# Teclado_numerico.net
KiCad netlist of a schematic drawn in Altium Designer
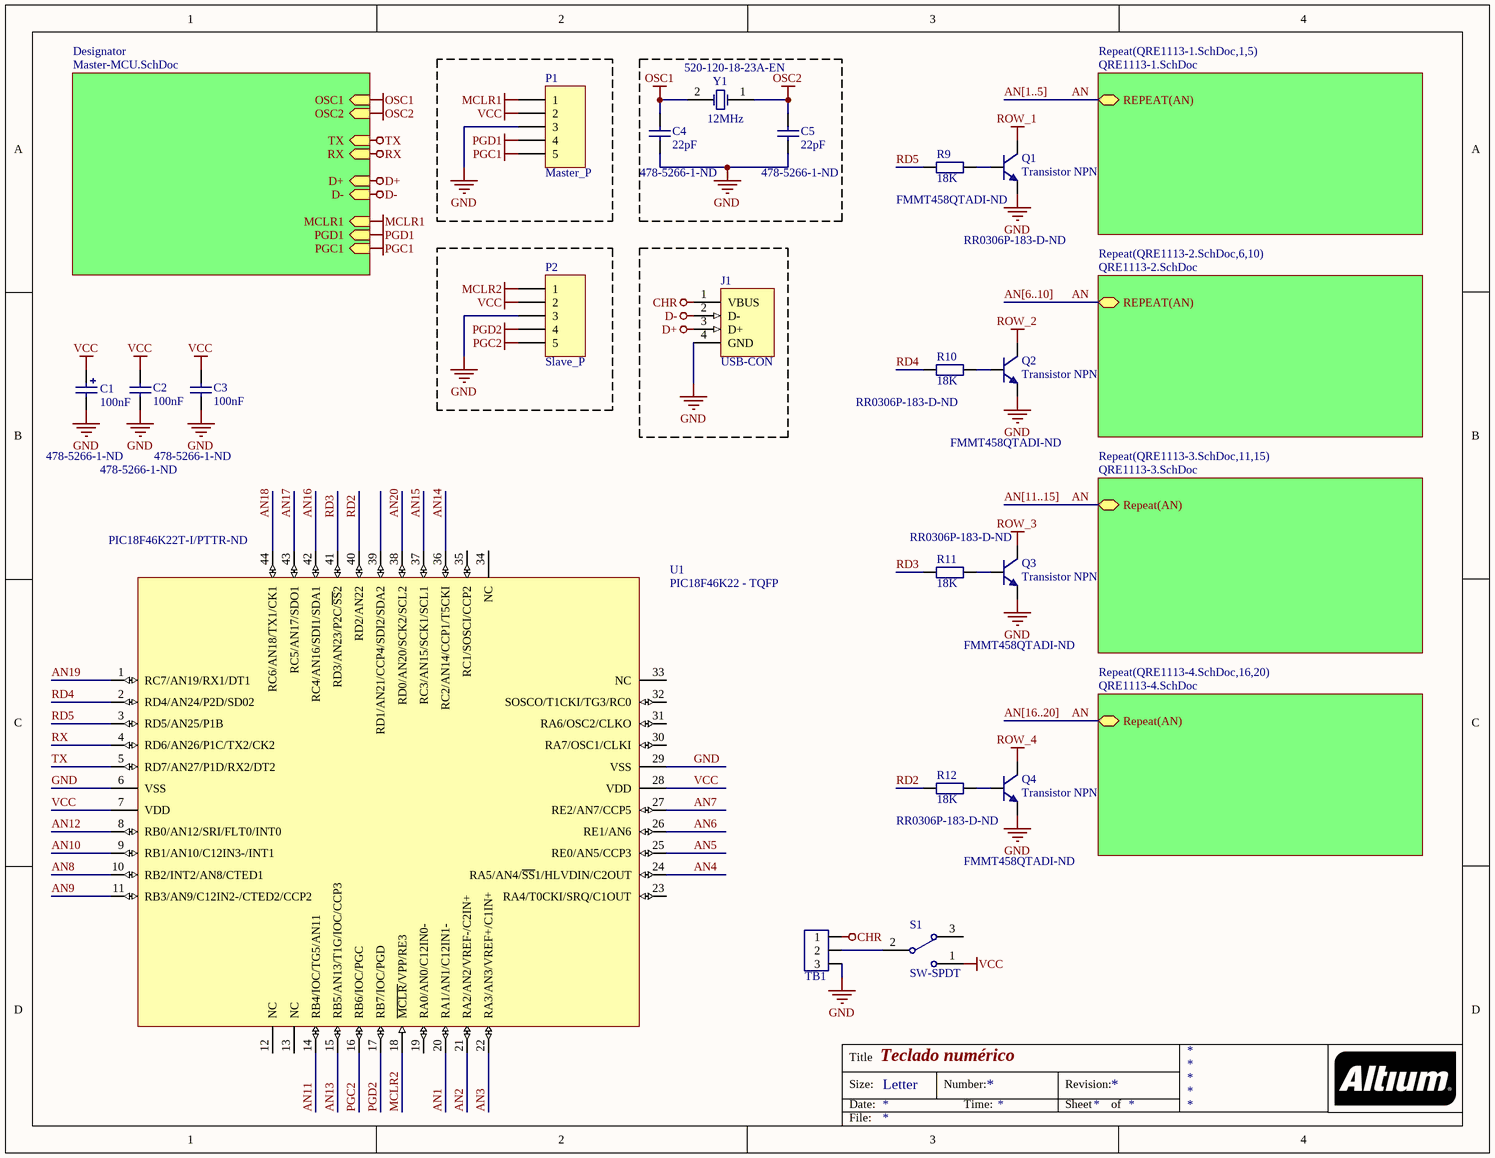
[diagram p0: Teclado numerico.SchDoc]

(export (version "E")
  (design (tool "Eeschema 10.0.6"))
  (components
    (comp (ref "C1")
      (value "100nF")
      (footprint "C-0603")
      (description "Electrolytic Capacitor")
      (fields (field (name "SUPPLIER PART NUMBER 1") "478-5266-1-ND"))
      (libsource (lib "Max Library") (part "Electrolytic Capacitor"))
    )
    (comp (ref "C2")
      (value "100nF")
      (footprint "C-0603")
      (description "Capacitor")
      (fields (field (name "SUPPLIER PART NUMBER 1") "478-5266-1-ND"))
      (libsource (lib "Max Library") (part "Capacitor 1"))
    )
    (comp (ref "C3")
      (value "100nF")
      (footprint "C-0603")
      (description "Capacitor")
      (fields (field (name "SUPPLIER PART NUMBER 1") "478-5266-1-ND"))
      (libsource (lib "Max Library") (part "Capacitor 1"))
    )
    (comp (ref "C4")
      (value "22pF")
      (footprint "C-0603")
      (description "Capacitor")
      (fields (field (name "SUPPLIER PART NUMBER 1") "478-5266-1-ND"))
      (libsource (lib "Max Library") (part "Capacitor 1"))
    )
    (comp (ref "C5")
      (value "22pF")
      (footprint "C-0603")
      (description "Capacitor")
      (fields (field (name "SUPPLIER PART NUMBER 1") "478-5266-1-ND"))
      (libsource (lib "Max Library") (part "Capacitor 1"))
    )
    (comp (ref "J1")
      (value "USB-CON")
      (footprint "JV Footprints:USB-A")
      (description "USB 1.1, Right Angle, SMT, A Type, Receptacle, 4 Position, White")
      (fields (field (name "PUBLISHER") "Altium Limited"))
      (libsource (lib "Max Library") (part "USB-CON"))
    )
    (comp (ref "P1")
      (value "Master_P")
      (footprint "HDR1X5")
      (description "Header, 5-Pin")
      (fields (field (name "PUBLISHER") "Altium Limited"))
      (libsource (lib "Miscellaneous Connectors") (part "Header 5"))
    )
    (comp (ref "P2")
      (value "Slave_P")
      (footprint "HDR1X5")
      (description "Header, 5-Pin")
      (fields (field (name "PUBLISHER") "Altium Limited"))
      (libsource (lib "Miscellaneous Connectors") (part "Header 5"))
    )
    (comp (ref "Q1")
      (value "Transistor NPN")
      (footprint "SOT95P237X111-3M-JV")
      (description "NPN General Purpose Amplifier")
      (fields
        (field (name "SUPPLIER PART NUMBER 1") "FMMT458QTADI-ND")
        (field (name "PUBLISHER") "Altium Limited")
      )
      (libsource (lib "Max Library") (part "Transistor NPN"))
    )
    (comp (ref "Q2")
      (value "Transistor NPN")
      (footprint "SOT95P237X111-3M-JV")
      (description "NPN General Purpose Amplifier")
      (fields
        (field (name "SUPPLIER PART NUMBER 1") "FMMT458QTADI-ND")
        (field (name "PUBLISHER") "Altium Limited")
      )
      (libsource (lib "Max Library") (part "Transistor NPN"))
    )
    (comp (ref "Q3")
      (value "Transistor NPN")
      (footprint "SOT95P237X111-3M-JV")
      (description "NPN General Purpose Amplifier")
      (fields
        (field (name "SUPPLIER PART NUMBER 1") "FMMT458QTADI-ND")
        (field (name "PUBLISHER") "Altium Limited")
      )
      (libsource (lib "Max Library") (part "Transistor NPN"))
    )
    (comp (ref "Q4")
      (value "Transistor NPN")
      (footprint "SOT95P237X111-3M-JV")
      (description "NPN General Purpose Amplifier")
      (fields
        (field (name "SUPPLIER PART NUMBER 1") "FMMT458QTADI-ND")
        (field (name "PUBLISHER") "Altium Limited")
      )
      (libsource (lib "Max Library") (part "Transistor NPN"))
    )
    (comp (ref "R9")
      (value "18K")
      (footprint "R-0603")
      (description "Resistor")
      (fields (field (name "SUPPLIER PART NUMBER 1") "RR0306P-183-D-ND"))
      (libsource (lib "Max Library") (part "Resistor 1"))
    )
    (comp (ref "R10")
      (value "18K")
      (footprint "R-0603")
      (description "Resistor")
      (fields (field (name "SUPPLIER PART NUMBER 1") "RR0306P-183-D-ND"))
      (libsource (lib "Max Library") (part "Resistor 1"))
    )
    (comp (ref "R11")
      (value "18K")
      (footprint "R-0603")
      (description "Resistor")
      (fields (field (name "SUPPLIER PART NUMBER 1") "RR0306P-183-D-ND"))
      (libsource (lib "Max Library") (part "Resistor 1"))
    )
    (comp (ref "R12")
      (value "18K")
      (footprint "R-0603")
      (description "Resistor")
      (fields (field (name "SUPPLIER PART NUMBER 1") "RR0306P-183-D-ND"))
      (libsource (lib "Max Library") (part "Resistor 1"))
    )
    (comp (ref "S1")
      (value "SW-SPDT")
      (footprint "SPDT:SPDT")
      (description "SPDT Subminiature Toggle Switch, Right Angle Mounting, Vertical Actuation")
      (fields (field (name "PUBLISHER") "Altium Limited"))
      (libsource (lib "Max Library") (part "SW-SPDT"))
    )
    (comp (ref "TB1")
      (value "Terminal Block 3")
      (footprint "SPDT:SPDT")
      (description "Terminal Block, 3 pins")
      (libsource (lib "Max Library") (part "Terminal Block 3"))
    )
    (comp (ref "U1")
      (value "PIC18F46K22 - TQFP")
      (footprint "JV Footprints:TQFP-44_JV")
      (fields
        (field (name "SUPPLIER PART NUMBER 3") "PIC18F46K22T-I/PTTR-ND")
        (field (name "PUBLISHER") "Altium Limited")
      )
      (libsource (lib "Microcontrollers Library 8-bit PIC18") (part "PIC18F46K22 - TQFP"))
    )
    (comp (ref "Y1")
      (value "12MHz")
      (footprint "JV Footprints:ECX64A-jv")
      (description "Crystal Oscillator")
      (fields
        (field (name "SUPPLIER PART NUMBER 1") "520-120-18-23A-EN")
        (field (name "PUBLISHER") "Altium Limited")
      )
      (libsource (lib "Max Library") (part "XTAL"))
    )
  )
  (nets
    (net (code "2") (name "/AN1") (class "Default")
      (node (ref "U1") (pin "20") (pinfunction "RA1/AN1/C12IN1-_20") (pintype "bidirectional"))
    )
    (net (code "3") (name "/AN2") (class "Default")
      (node (ref "U1") (pin "21") (pinfunction "RA2/AN2/VREF-/C2IN+_21") (pintype "bidirectional"))
    )
    (net (code "4") (name "/AN3") (class "Default")
      (node (ref "U1") (pin "22") (pinfunction "RA3/AN3/VREF+/C1IN+_22") (pintype "bidirectional"))
    )
    (net (code "5") (name "/AN4") (class "Default")
      (node (ref "U1") (pin "24") (pinfunction "RA5/AN4/~{SS}1/HLVDIN/C2OUT_24") (pintype "bidirectional"))
    )
    (net (code "6") (name "/AN5") (class "Default")
      (node (ref "U1") (pin "25") (pinfunction "RE0/AN5/CCP3_25") (pintype "bidirectional"))
    )
    (net (code "7") (name "/AN6") (class "Default")
      (node (ref "U1") (pin "26") (pinfunction "RE1/AN6_26") (pintype "bidirectional"))
    )
    (net (code "8") (name "/AN7") (class "Default")
      (node (ref "U1") (pin "27") (pinfunction "RE2/AN7/CCP5_27") (pintype "bidirectional"))
    )
    (net (code "9") (name "/AN8") (class "Default")
      (node (ref "U1") (pin "10") (pinfunction "RB2/INT2/AN8/CTED1_10") (pintype "bidirectional"))
    )
    (net (code "10") (name "/AN9") (class "Default")
      (node (ref "U1") (pin "11") (pinfunction "RB3/AN9/C12IN2-/CTED2/CCP2_11") (pintype "bidirectional"))
    )
    (net (code "11") (name "/AN10") (class "Default")
      (node (ref "U1") (pin "9") (pinfunction "RB1/AN10/C12IN3-/INT1_9") (pintype "bidirectional"))
    )
    (net (code "12") (name "/AN11") (class "Default")
      (node (ref "U1") (pin "14") (pinfunction "RB4/IOC/TG5/AN11_14") (pintype "bidirectional"))
    )
    (net (code "13") (name "/AN12") (class "Default")
      (node (ref "U1") (pin "8") (pinfunction "RB0/AN12/SRI/FLT0/INT0_8") (pintype "bidirectional"))
    )
    (net (code "14") (name "/AN13") (class "Default")
      (node (ref "U1") (pin "15") (pinfunction "RB5/AN13/T1G/IOC/CCP3_15") (pintype "bidirectional"))
    )
    (net (code "15") (name "/AN14") (class "Default")
      (node (ref "U1") (pin "36") (pinfunction "RC2/AN14/CCP1/T5CKI_36") (pintype "bidirectional"))
    )
    (net (code "16") (name "/AN15") (class "Default")
      (node (ref "U1") (pin "37") (pinfunction "RC3/AN15/SCK1/SCL1_37") (pintype "bidirectional"))
    )
    (net (code "17") (name "/AN16") (class "Default")
      (node (ref "U1") (pin "42") (pinfunction "RC4/AN16/SDI1/SDA1_42") (pintype "bidirectional"))
    )
    (net (code "18") (name "/AN17") (class "Default")
      (node (ref "U1") (pin "43") (pinfunction "RC5/AN17/SDO1_43") (pintype "bidirectional"))
    )
    (net (code "19") (name "/AN18") (class "Default")
      (node (ref "U1") (pin "44") (pinfunction "RC6/AN18/TX1/CK1_44") (pintype "bidirectional"))
    )
    (net (code "20") (name "/AN19") (class "Default")
      (node (ref "U1") (pin "1") (pinfunction "RC7/AN19/RX1/DT1_1") (pintype "bidirectional"))
    )
    (net (code "21") (name "/AN20") (class "Default")
      (node (ref "U1") (pin "38") (pinfunction "RD0/AN20/SCK2/SCL2_38") (pintype "bidirectional"))
    )
    (net (code "26") (name "/RD2") (class "Default")
      (node (ref "R12") (pin "1") (pinfunction "1_1") (pintype "passive"))
      (node (ref "U1") (pin "40") (pinfunction "RD2/AN22_40") (pintype "bidirectional"))
    )
    (net (code "27") (name "/RD3") (class "Default")
      (node (ref "R11") (pin "1") (pinfunction "1_1") (pintype "passive"))
      (node (ref "U1") (pin "41") (pinfunction "RD3/AN23/P2C/~{SS}2_41") (pintype "bidirectional"))
    )
    (net (code "28") (name "/RD4") (class "Default")
      (node (ref "R10") (pin "1") (pinfunction "1_1") (pintype "passive"))
      (node (ref "U1") (pin "2") (pinfunction "RD4/AN24/P2D/SD02_2") (pintype "bidirectional"))
    )
    (net (code "29") (name "/RD5") (class "Default")
      (node (ref "R9") (pin "1") (pinfunction "1_1") (pintype "passive"))
      (node (ref "U1") (pin "3") (pinfunction "RD5/AN25/P1B_3") (pintype "bidirectional"))
    )
    (net (code "30") (name "CHR") (class "Default")
      (node (ref "J1") (pin "1") (pinfunction "VBUS_1") (pintype "power_in"))
      (node (ref "TB1") (pin "1") (pinfunction "1_1") (pintype "passive"))
    )
    (net (code "31") (name "D+") (class "Default")
      (node (ref "J1") (pin "3") (pinfunction "D+_3") (pintype "input"))
    )
    (net (code "32") (name "D-") (class "Default")
      (node (ref "J1") (pin "2") (pinfunction "D-_2") (pintype "input"))
    )
    (net (code "33") (name "GND") (class "Default")
      (node (ref "C1") (pin "2") (pinfunction "2_2") (pintype "passive"))
      (node (ref "C2") (pin "1") (pinfunction "1_1") (pintype "passive"))
      (node (ref "C3") (pin "1") (pinfunction "1_1") (pintype "passive"))
      (node (ref "C4") (pin "2") (pinfunction "2_2") (pintype "passive"))
      (node (ref "C5") (pin "2") (pinfunction "2_2") (pintype "passive"))
      (node (ref "J1") (pin "4") (pinfunction "GND_4") (pintype "power_in"))
      (node (ref "P1") (pin "3") (pinfunction "3_3") (pintype "passive"))
      (node (ref "P2") (pin "3") (pinfunction "3_3") (pintype "passive"))
      (node (ref "Q1") (pin "1") (pinfunction "E_1") (pintype "passive"))
      (node (ref "Q2") (pin "1") (pinfunction "E_1") (pintype "passive"))
      (node (ref "Q3") (pin "1") (pinfunction "E_1") (pintype "passive"))
      (node (ref "Q4") (pin "1") (pinfunction "E_1") (pintype "passive"))
      (node (ref "TB1") (pin "3") (pinfunction "3_3") (pintype "passive"))
      (node (ref "U1") (pin "29") (pinfunction "VSS_29") (pintype "power_in"))
      (node (ref "U1") (pin "6") (pinfunction "VSS_6") (pintype "power_in"))
    )
    (net (code "34") (name "MCLR1") (class "Default")
      (node (ref "P1") (pin "1") (pinfunction "1_1") (pintype "passive"))
    )
    (net (code "35") (name "MCLR2") (class "Default")
      (node (ref "P2") (pin "1") (pinfunction "1_1") (pintype "passive"))
      (node (ref "U1") (pin "18") (pinfunction "~{MCLR}/VPP/RE3_18") (pintype "input"))
    )
    (net (code "36") (name "Net-(Q1-B)") (class "Default")
      (node (ref "Q1") (pin "2") (pinfunction "B_2") (pintype "passive"))
      (node (ref "R9") (pin "2") (pinfunction "2_2") (pintype "passive"))
    )
    (net (code "37") (name "Net-(Q2-B)") (class "Default")
      (node (ref "Q2") (pin "2") (pinfunction "B_2") (pintype "passive"))
      (node (ref "R10") (pin "2") (pinfunction "2_2") (pintype "passive"))
    )
    (net (code "38") (name "Net-(Q3-B)") (class "Default")
      (node (ref "Q3") (pin "2") (pinfunction "B_2") (pintype "passive"))
      (node (ref "R11") (pin "2") (pinfunction "2_2") (pintype "passive"))
    )
    (net (code "39") (name "Net-(Q4-B)") (class "Default")
      (node (ref "Q4") (pin "2") (pinfunction "B_2") (pintype "passive"))
      (node (ref "R12") (pin "2") (pinfunction "2_2") (pintype "passive"))
    )
    (net (code "40") (name "Net-(S1-Pad2)") (class "Default")
      (node (ref "S1") (pin "2") (pinfunction "2_2") (pintype "passive"))
      (node (ref "TB1") (pin "2") (pinfunction "2_2") (pintype "passive"))
    )
    (net (code "41") (name "OSC1") (class "Default")
      (node (ref "C4") (pin "1") (pinfunction "1_1") (pintype "passive"))
      (node (ref "Y1") (pin "2") (pinfunction "OSC2_2") (pintype "passive"))
    )
    (net (code "42") (name "OSC2") (class "Default")
      (node (ref "C5") (pin "1") (pinfunction "1_1") (pintype "passive"))
      (node (ref "Y1") (pin "1") (pinfunction "OSC1_1") (pintype "passive"))
    )
    (net (code "43") (name "PGC1") (class "Default")
      (node (ref "P1") (pin "5") (pinfunction "5_5") (pintype "passive"))
    )
    (net (code "44") (name "PGC2") (class "Default")
      (node (ref "P2") (pin "5") (pinfunction "5_5") (pintype "passive"))
      (node (ref "U1") (pin "16") (pinfunction "RB6/IOC/PGC_16") (pintype "bidirectional"))
    )
    (net (code "45") (name "PGD1") (class "Default")
      (node (ref "P1") (pin "4") (pinfunction "4_4") (pintype "passive"))
    )
    (net (code "46") (name "PGD2") (class "Default")
      (node (ref "P2") (pin "4") (pinfunction "4_4") (pintype "passive"))
      (node (ref "U1") (pin "17") (pinfunction "RB7/IOC/PGD_17") (pintype "bidirectional"))
    )
    (net (code "47") (name "ROW_1") (class "Default")
      (node (ref "Q1") (pin "3") (pinfunction "C_3") (pintype "passive"))
    )
    (net (code "48") (name "ROW_2") (class "Default")
      (node (ref "Q2") (pin "3") (pinfunction "C_3") (pintype "passive"))
    )
    (net (code "49") (name "ROW_3") (class "Default")
      (node (ref "Q3") (pin "3") (pinfunction "C_3") (pintype "passive"))
    )
    (net (code "50") (name "ROW_4") (class "Default")
      (node (ref "Q4") (pin "3") (pinfunction "C_3") (pintype "passive"))
    )
    (net (code "51") (name "RX") (class "Default")
      (node (ref "U1") (pin "4") (pinfunction "RD6/AN26/P1C/TX2/CK2_4") (pintype "bidirectional"))
    )
    (net (code "52") (name "TX") (class "Default")
      (node (ref "U1") (pin "5") (pinfunction "RD7/AN27/P1D/RX2/DT2_5") (pintype "bidirectional"))
    )
    (net (code "53") (name "VCC") (class "Default")
      (node (ref "C1") (pin "1") (pinfunction "1_1") (pintype "passive"))
      (node (ref "C2") (pin "2") (pinfunction "2_2") (pintype "passive"))
      (node (ref "C3") (pin "2") (pinfunction "2_2") (pintype "passive"))
      (node (ref "P1") (pin "2") (pinfunction "2_2") (pintype "passive"))
      (node (ref "P2") (pin "2") (pinfunction "2_2") (pintype "passive"))
      (node (ref "S1") (pin "1") (pinfunction "1_1") (pintype "passive"))
      (node (ref "U1") (pin "28") (pinfunction "VDD_28") (pintype "power_in"))
      (node (ref "U1") (pin "7") (pinfunction "VDD_7") (pintype "power_in"))
    )
    (net (code "54") (name "unconnected-(S1-Pad3)") (class "Default")
      (node (ref "S1") (pin "3") (pinfunction "3_3") (pintype "passive"))
    )
    (net (code "55") (name "unconnected-(U1-NC-Pad12)") (class "Default")
      (node (ref "U1") (pin "12") (pinfunction "NC_12") (pintype "passive"))
    )
    (net (code "56") (name "unconnected-(U1-NC-Pad13)") (class "Default")
      (node (ref "U1") (pin "13") (pinfunction "NC_13") (pintype "passive"))
    )
    (net (code "57") (name "unconnected-(U1-NC-Pad33)") (class "Default")
      (node (ref "U1") (pin "33") (pinfunction "NC_33") (pintype "passive"))
    )
    (net (code "58") (name "unconnected-(U1-NC-Pad34)") (class "Default")
      (node (ref "U1") (pin "34") (pinfunction "NC_34") (pintype "passive"))
    )
    (net (code "59") (name "unconnected-(U1-RA0{slash}AN0{slash}C12IN0--Pad19)") (class "Default")
      (node (ref "U1") (pin "19") (pinfunction "RA0/AN0/C12IN0-_19") (pintype "bidirectional"))
    )
    (net (code "60") (name "unconnected-(U1-RA4{slash}T0CKI{slash}SRQ{slash}C1OUT-Pad23)") (class "Default")
      (node (ref "U1") (pin "23") (pinfunction "RA4/T0CKI/SRQ/C1OUT_23") (pintype "bidirectional"))
    )
    (net (code "61") (name "unconnected-(U1-RA6{slash}OSC2{slash}CLKO-Pad31)") (class "Default")
      (node (ref "U1") (pin "31") (pinfunction "RA6/OSC2/CLKO_31") (pintype "bidirectional"))
    )
    (net (code "62") (name "unconnected-(U1-RA7{slash}OSC1{slash}CLKI-Pad30)") (class "Default")
      (node (ref "U1") (pin "30") (pinfunction "RA7/OSC1/CLKI_30") (pintype "bidirectional"))
    )
    (net (code "63") (name "unconnected-(U1-RC1{slash}SOSCI{slash}CCP2-Pad35)") (class "Default")
      (node (ref "U1") (pin "35") (pinfunction "RC1/SOSCI/CCP2_35") (pintype "bidirectional"))
    )
    (net (code "64") (name "unconnected-(U1-RD1{slash}AN21{slash}CCP4{slash}SDI2{slash}SDA2-Pad39)") (class "Default")
      (node (ref "U1") (pin "39") (pinfunction "RD1/AN21/CCP4/SDI2/SDA2_39") (pintype "bidirectional"))
    )
    (net (code "65") (name "unconnected-(U1-SOSCO{slash}T1CKI{slash}TG3{slash}RC0-Pad32)") (class "Default")
      (node (ref "U1") (pin "32") (pinfunction "SOSCO/T1CKI/TG3/RC0_32") (pintype "bidirectional"))
    )
  )
)
